# Sheet1.net
KiCad netlist of a schematic drawn in Altium Designer
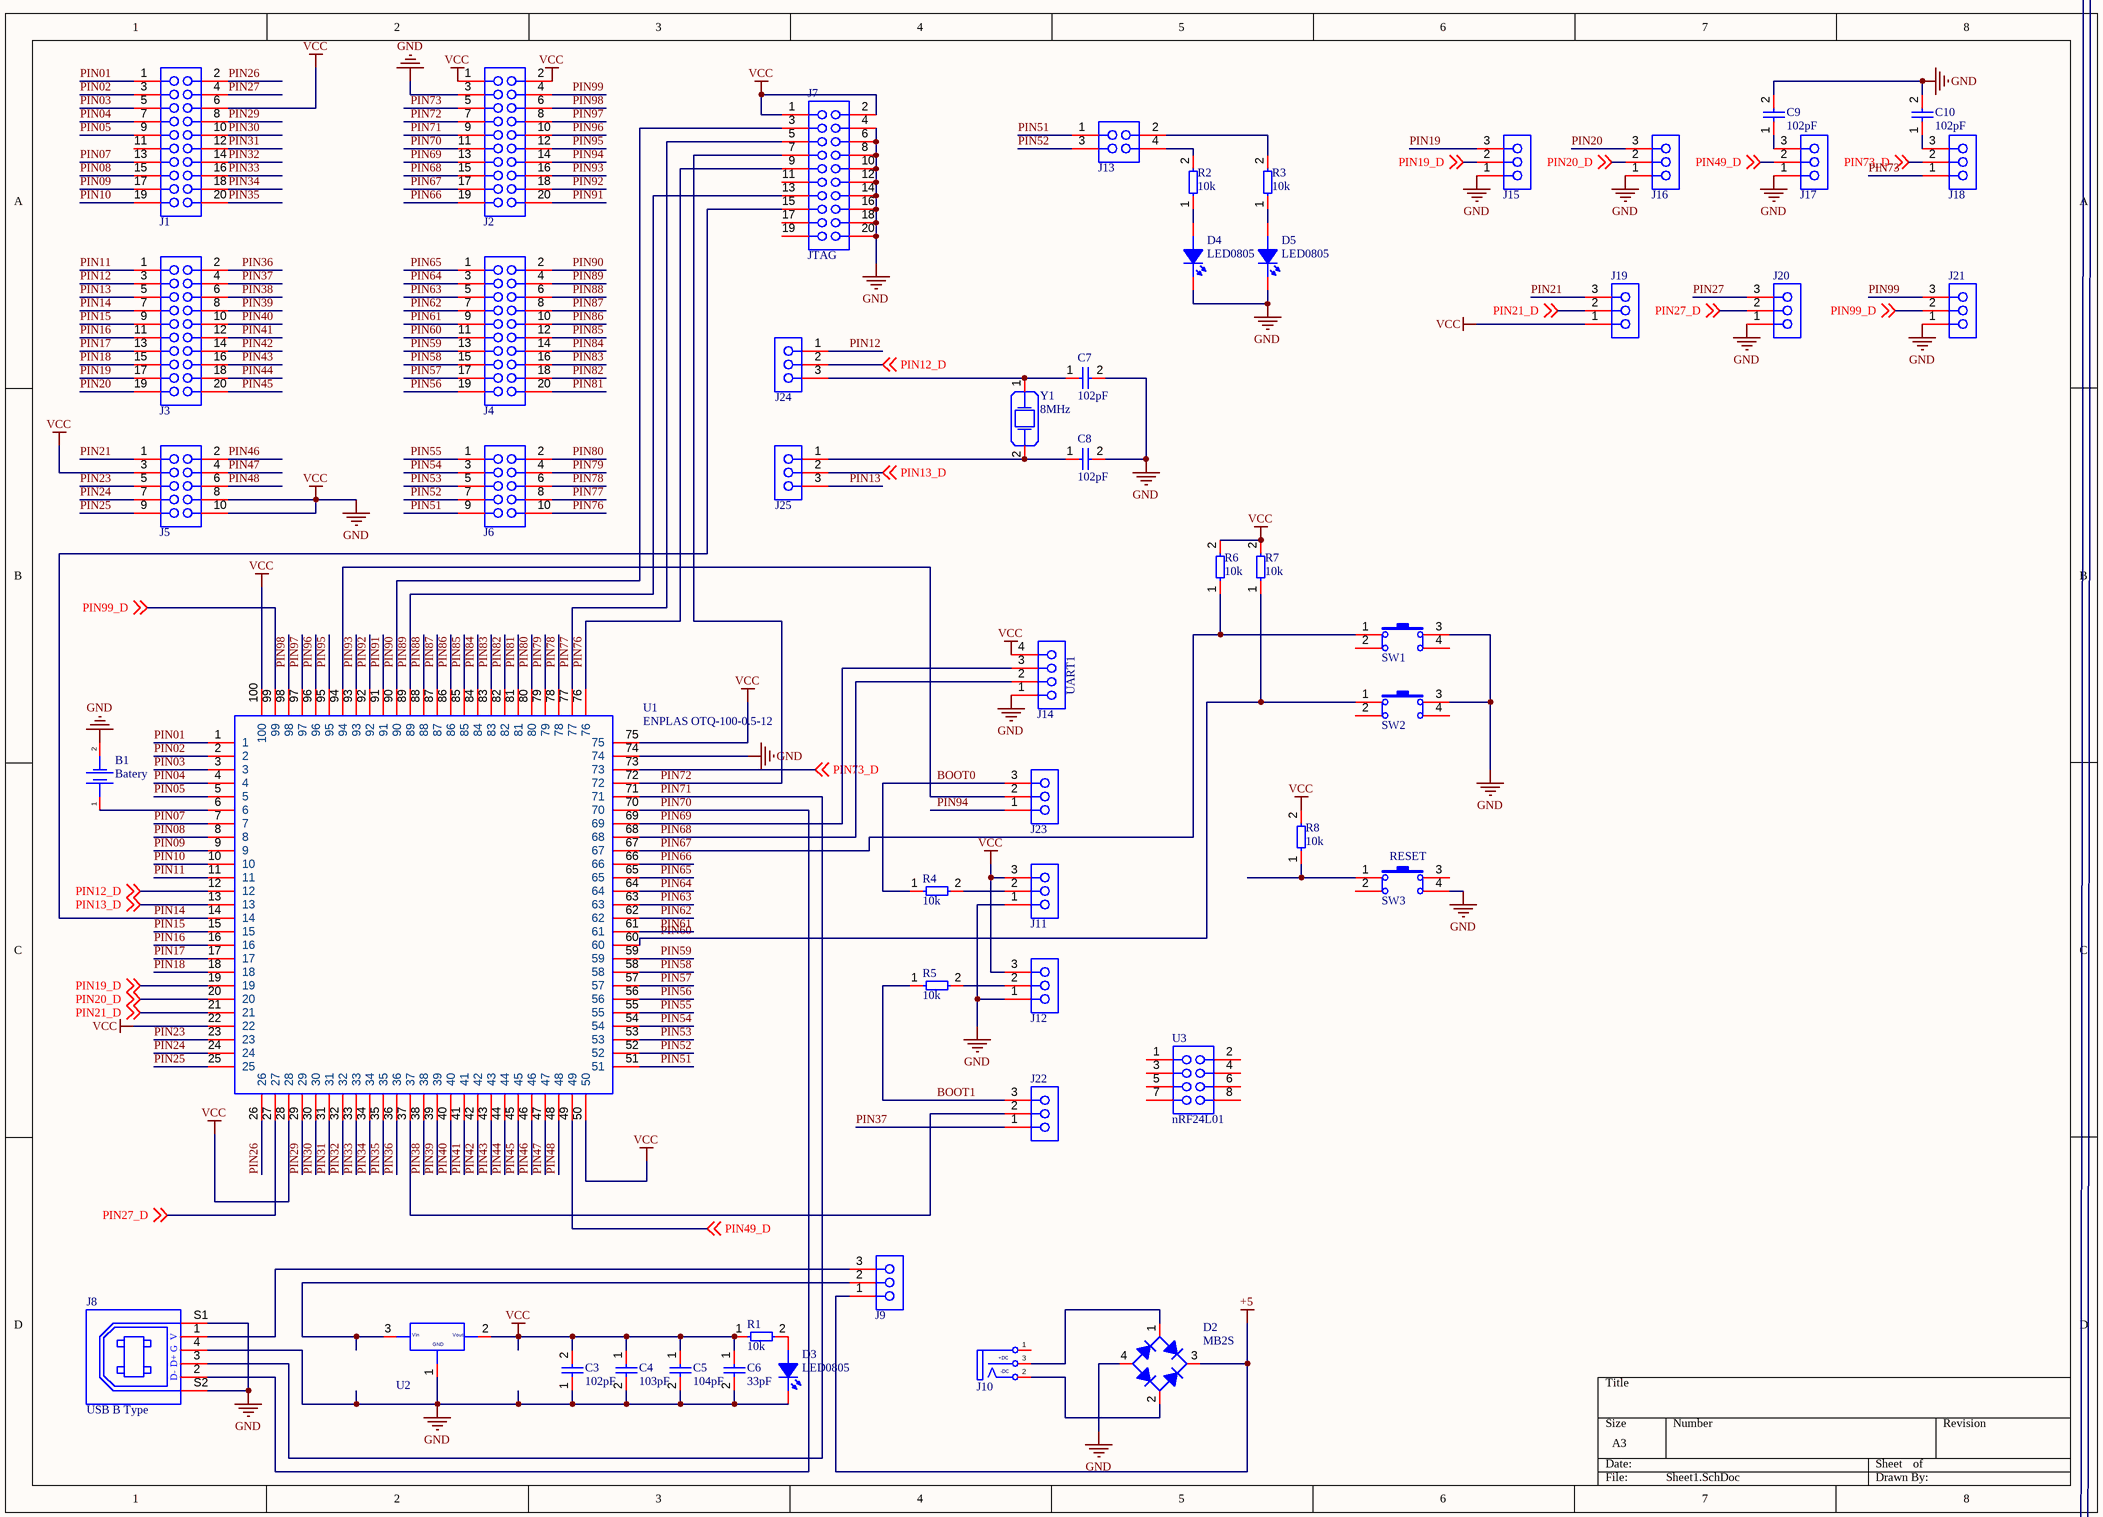
[diagram p0: Sheet1.SchDoc]

(export (version "E")
  (design (tool "Eeschema 10.0.6"))
  (components
    (comp (ref "B1") (value "Batery") (footprint "CR1220") (libsource (lib "SMDLibrary") (part "Batery")))
    (comp (ref "C3")
      (value "102pF")
      (footprint "C0805")
      (libsource (lib "SMDLibrary") (part "Capacitors(SMD)"))
    )
    (comp (ref "C4")
      (value "103pF")
      (footprint "C0805")
      (libsource (lib "SMDLibrary") (part "Capacitors(SMD)"))
    )
    (comp (ref "C5")
      (value "104pF")
      (footprint "C0805")
      (libsource (lib "SMDLibrary") (part "Capacitors(SMD)"))
    )
    (comp (ref "C6")
      (value "33pF")
      (footprint "C0805")
      (libsource (lib "SMDLibrary") (part "Capacitors(SMD)"))
    )
    (comp (ref "C7")
      (value "102pF")
      (footprint "C0805")
      (libsource (lib "SMDLibrary") (part "Capacitors(SMD)"))
    )
    (comp (ref "C8")
      (value "102pF")
      (footprint "C0805")
      (libsource (lib "SMDLibrary") (part "Capacitors(SMD)"))
    )
    (comp (ref "C9")
      (value "102pF")
      (footprint "C0805")
      (libsource (lib "SMDLibrary") (part "Capacitors(SMD)"))
    )
    (comp (ref "C10")
      (value "102pF")
      (footprint "C0805")
      (libsource (lib "SMDLibrary") (part "Capacitors(SMD)"))
    )
    (comp (ref "D2") (value "MB2S") (footprint "TO-269AA") (libsource (lib "SMDLibrary") (part "Diode MB2S")))
    (comp (ref "D3") (value "LED0805") (footprint "L0805RED") (libsource (lib "SMDLibrary") (part "LED0805")))
    (comp (ref "D4") (value "LED0805") (footprint "L0805RED") (libsource (lib "SMDLibrary") (part "LED0805")))
    (comp (ref "D5") (value "LED0805") (footprint "L0805RED") (libsource (lib "SMDLibrary") (part "LED0805")))
    (comp (ref "J1")
      (value "Header 10x2 TH Pitch 2.54mm")
      (footprint "Header 10x2 TH Pitch 2.54mm")
      (libsource (lib "SMDLibrary") (part "Header 10x2 TH Pitch 2.54mm"))
    )
    (comp (ref "J2")
      (value "Header 10x2 TH Pitch 2.54mm")
      (footprint "Header 10x2 TH Pitch 2.54mm")
      (libsource (lib "SMDLibrary") (part "Header 10x2 TH Pitch 2.54mm"))
    )
    (comp (ref "J3")
      (value "Header 10x2 TH Pitch 2.54mm")
      (footprint "Header 10x2 TH Pitch 2.54mm")
      (libsource (lib "SMDLibrary") (part "Header 10x2 TH Pitch 2.54mm"))
    )
    (comp (ref "J4")
      (value "Header 10x2 TH Pitch 2.54mm")
      (footprint "Header 10x2 TH Pitch 2.54mm")
      (libsource (lib "SMDLibrary") (part "Header 10x2 TH Pitch 2.54mm"))
    )
    (comp (ref "J5")
      (value "Header 5x2 TH Pitch 2.54mm")
      (footprint "Header 5x2 TH Pitch 2.54mm")
      (libsource (lib "SMDLibrary") (part "Header 5x2 TH Pitch 2.54mm"))
    )
    (comp (ref "J6")
      (value "Header 5x2 TH Pitch 2.54mm")
      (footprint "Header 5x2 TH Pitch 2.54mm")
      (libsource (lib "SMDLibrary") (part "Header 5x2 TH Pitch 2.54mm"))
    )
    (comp (ref "J7")
      (value "JTAG")
      (footprint "IDC_CONNECTOR_20_2.54")
      (libsource (lib "SMDLibrary") (part "IDC_2.54_10x2"))
    )
    (comp (ref "J8")
      (value "USB B Type")
      (footprint "USB-B-TYPE")
      (libsource (lib "SMDLibrary") (part "USB B Type"))
    )
    (comp (ref "J9")
      (value "Header 3x1 TH Pitch 2.54mm")
      (footprint "Header 3x1 TH Pitch 2.54mm")
      (libsource (lib "") (part "Header 3x1 TH Pitch 2.54mm_1"))
    )
    (comp (ref "J10")
      (value "Connector")
      (footprint "JACK-DC")
      (libsource (lib "SMDLibrary") (part "JackDC"))
    )
    (comp (ref "J11")
      (value "Header 3x1 TH Pitch 2.54mm")
      (footprint "Header 3x1 TH Pitch 2.54mm")
      (libsource (lib "") (part "Header 3x1 TH Pitch 2.54mm_1"))
    )
    (comp (ref "J12")
      (value "Header 3x1 TH Pitch 2.54mm")
      (footprint "Header 3x1 TH Pitch 2.54mm")
      (libsource (lib "") (part "Header 3x1 TH Pitch 2.54mm_1"))
    )
    (comp (ref "J13")
      (value "Header 2x2 TH Pitch 2.54mm")
      (footprint "Header 2x2 TH Pitch 2.54mm")
      (libsource (lib "SMDLibrary") (part "Header 2x2 TH Pitch 2.54mm"))
    )
    (comp (ref "J14")
      (value "UART1")
      (footprint "Header 4x1 TH Pitch 2.54mm")
      (libsource (lib "SMDLibrary") (part "Header 4x1 TH Pitch 2.54mm"))
    )
    (comp (ref "J15")
      (value "Header 3x1 TH Pitch 2.54mm")
      (footprint "Header 3x1 TH Pitch 2.54mm")
      (libsource (lib "") (part "Header 3x1 TH Pitch 2.54mm_1"))
    )
    (comp (ref "J16")
      (value "Header 3x1 TH Pitch 2.54mm")
      (footprint "Header 3x1 TH Pitch 2.54mm")
      (libsource (lib "") (part "Header 3x1 TH Pitch 2.54mm_1"))
    )
    (comp (ref "J17")
      (value "Header 3x1 TH Pitch 2.54mm")
      (footprint "Header 3x1 TH Pitch 2.54mm")
      (libsource (lib "") (part "Header 3x1 TH Pitch 2.54mm_1"))
    )
    (comp (ref "J18")
      (value "Header 3x1 TH Pitch 2.54mm")
      (footprint "Header 3x1 TH Pitch 2.54mm")
      (libsource (lib "") (part "Header 3x1 TH Pitch 2.54mm_1"))
    )
    (comp (ref "J19")
      (value "Header 3x1 TH Pitch 2.54mm")
      (footprint "Header 3x1 TH Pitch 2.54mm")
      (libsource (lib "") (part "Header 3x1 TH Pitch 2.54mm_1"))
    )
    (comp (ref "J20")
      (value "Header 3x1 TH Pitch 2.54mm")
      (footprint "Header 3x1 TH Pitch 2.54mm")
      (libsource (lib "") (part "Header 3x1 TH Pitch 2.54mm_1"))
    )
    (comp (ref "J21")
      (value "Header 3x1 TH Pitch 2.54mm")
      (footprint "Header 3x1 TH Pitch 2.54mm")
      (libsource (lib "") (part "Header 3x1 TH Pitch 2.54mm_1"))
    )
    (comp (ref "J22")
      (value "Header 3x1 TH Pitch 2.54mm")
      (footprint "Header 3x1 TH Pitch 2.54mm")
      (libsource (lib "") (part "Header 3x1 TH Pitch 2.54mm_1"))
    )
    (comp (ref "J23")
      (value "Header 3x1 TH Pitch 2.54mm")
      (footprint "Header 3x1 TH Pitch 2.54mm")
      (libsource (lib "") (part "Header 3x1 TH Pitch 2.54mm_1"))
    )
    (comp (ref "J24")
      (value "Header 3x1 TH Pitch 2.54mm")
      (footprint "Header 3x1 TH Pitch 2.54mm")
      (libsource (lib "SMDLibrary") (part "Header 3x1 TH Pitch 2.54mm"))
    )
    (comp (ref "J25")
      (value "Header 3x1 TH Pitch 2.54mm")
      (footprint "Header 3x1 TH Pitch 2.54mm")
      (libsource (lib "SMDLibrary") (part "Header 3x1 TH Pitch 2.54mm"))
    )
    (comp (ref "R1") (value "10k") (footprint "R0805") (libsource (lib "SMDLibrary") (part "Resistor SMD")))
    (comp (ref "R2") (value "10k") (footprint "R0805") (libsource (lib "") (part "Resistor SMD_1")))
    (comp (ref "R3") (value "10k") (footprint "R0805") (libsource (lib "") (part "Resistor SMD_1")))
    (comp (ref "R4") (value "10k") (footprint "R0805") (libsource (lib "SMDLibrary") (part "Resistor SMD")))
    (comp (ref "R5") (value "10k") (footprint "R0805") (libsource (lib "SMDLibrary") (part "Resistor SMD")))
    (comp (ref "R6") (value "10k") (footprint "R0805") (libsource (lib "") (part "Resistor SMD_1")))
    (comp (ref "R7") (value "10k") (footprint "R0805") (libsource (lib "") (part "Resistor SMD_1")))
    (comp (ref "R8") (value "10k") (footprint "R0805") (libsource (lib "") (part "Resistor SMD_1")))
    (comp (ref "SW1")
      (value "Button Hole")
      (footprint "BUTTON_HOLE_5.0mm")
      (libsource (lib "SMDLibrary") (part "Button Hole"))
    )
    (comp (ref "SW2")
      (value "Button Hole")
      (footprint "BUTTON_HOLE_5.0mm")
      (libsource (lib "SMDLibrary") (part "Button Hole"))
    )
    (comp (ref "SW3")
      (value "RESET")
      (footprint "BUTTON_HOLE_5.0mm")
      (libsource (lib "SMDLibrary") (part "Button Hole"))
    )
    (comp (ref "U1")
      (value "ENPLAS OTQ-100-0.5-12")
      (footprint "ENPLAS OTQ-100-0.5-12-00 IC SOCKET")
      (libsource (lib "SMDLibrary") (part "ENPLAS OTQ-100-0.5-12-00 IC SOCKET"))
    )
    (comp (ref "U2")
      (value "AMS1117")
      (footprint "SOT223-3")
      (libsource (lib "SMDLibrary") (part "AMS1117(SOT-223)"))
    )
    (comp (ref "U3")
      (value "nRF24L01")
      (footprint "nRF24L01")
      (libsource (lib "SMDLibrary") (part "nRF24L01"))
    )
    (comp (ref "Y1")
      (value "8MHz")
      (footprint "HC-49_THROUGH")
      (libsource (lib "SMDLibrary") (part "Crystal"))
    )
  )
  (nets
    (net (code "1") (name "+5") (class "Default")
      (node (ref "D2") (pin "3") (pinfunction "3_3") (pintype "passive"))
      (node (ref "J9") (pin "1") (pinfunction "1_1") (pintype "passive"))
    )
    (net (code "2") (name "/BOOT0") (class "Default")
      (node (ref "J23") (pin "3") (pinfunction "3_3") (pintype "passive"))
      (node (ref "R4") (pin "1") (pinfunction "1_1") (pintype "passive"))
    )
    (net (code "3") (name "/BOOT1") (class "Default")
      (node (ref "J22") (pin "3") (pinfunction "3_3") (pintype "passive"))
      (node (ref "R5") (pin "1") (pinfunction "1_1") (pintype "passive"))
    )
    (net (code "4") (name "/PIN01") (class "Default")
      (node (ref "J1") (pin "1") (pinfunction "1_1") (pintype "passive"))
      (node (ref "U1") (pin "1") (pinfunction "1_1") (pintype "passive"))
    )
    (net (code "5") (name "/PIN02") (class "Default")
      (node (ref "J1") (pin "3") (pinfunction "3_3") (pintype "passive"))
      (node (ref "U1") (pin "2") (pinfunction "2_2") (pintype "passive"))
    )
    (net (code "6") (name "/PIN03") (class "Default")
      (node (ref "J1") (pin "5") (pinfunction "5_5") (pintype "passive"))
      (node (ref "U1") (pin "3") (pinfunction "3_3") (pintype "passive"))
    )
    (net (code "7") (name "/PIN04") (class "Default")
      (node (ref "J1") (pin "7") (pinfunction "7_7") (pintype "passive"))
      (node (ref "U1") (pin "4") (pinfunction "4_4") (pintype "passive"))
    )
    (net (code "8") (name "/PIN05") (class "Default")
      (node (ref "J1") (pin "9") (pinfunction "9_9") (pintype "passive"))
      (node (ref "U1") (pin "5") (pinfunction "5_5") (pintype "passive"))
    )
    (net (code "9") (name "/PIN07") (class "Default")
      (node (ref "J1") (pin "13") (pinfunction "13_13") (pintype "passive"))
      (node (ref "U1") (pin "7") (pinfunction "7_7") (pintype "passive"))
    )
    (net (code "10") (name "/PIN08") (class "Default")
      (node (ref "J1") (pin "15") (pinfunction "15_15") (pintype "passive"))
      (node (ref "U1") (pin "8") (pinfunction "8_8") (pintype "passive"))
    )
    (net (code "11") (name "/PIN09") (class "Default")
      (node (ref "J1") (pin "17") (pinfunction "17_17") (pintype "passive"))
      (node (ref "U1") (pin "9") (pinfunction "9_9") (pintype "passive"))
    )
    (net (code "12") (name "/PIN10") (class "Default")
      (node (ref "J1") (pin "19") (pinfunction "19_19") (pintype "passive"))
      (node (ref "U1") (pin "10") (pinfunction "10_10") (pintype "passive"))
    )
    (net (code "13") (name "/PIN11") (class "Default")
      (node (ref "J3") (pin "1") (pinfunction "1_1") (pintype "passive"))
      (node (ref "U1") (pin "11") (pinfunction "11_11") (pintype "passive"))
    )
    (net (code "14") (name "/PIN12") (class "Default")
      (node (ref "J24") (pin "1") (pinfunction "1_1") (pintype "passive"))
      (node (ref "J3") (pin "3") (pinfunction "3_3") (pintype "passive"))
    )
    (net (code "15") (name "/PIN13") (class "Default")
      (node (ref "J25") (pin "3") (pinfunction "3_3") (pintype "passive"))
      (node (ref "J3") (pin "5") (pinfunction "5_5") (pintype "passive"))
    )
    (net (code "16") (name "/PIN14") (class "Default")
      (node (ref "J3") (pin "7") (pinfunction "7_7") (pintype "passive"))
      (node (ref "J7") (pin "15") (pinfunction "15_15") (pintype "passive"))
      (node (ref "U1") (pin "14") (pinfunction "14_14") (pintype "passive"))
    )
    (net (code "17") (name "/PIN15") (class "Default")
      (node (ref "J3") (pin "9") (pinfunction "9_9") (pintype "passive"))
      (node (ref "U1") (pin "15") (pinfunction "15_15") (pintype "passive"))
    )
    (net (code "18") (name "/PIN16") (class "Default")
      (node (ref "J3") (pin "11") (pinfunction "11_11") (pintype "passive"))
      (node (ref "U1") (pin "16") (pinfunction "16_16") (pintype "passive"))
    )
    (net (code "19") (name "/PIN17") (class "Default")
      (node (ref "J3") (pin "13") (pinfunction "13_13") (pintype "passive"))
      (node (ref "U1") (pin "17") (pinfunction "17_17") (pintype "passive"))
    )
    (net (code "20") (name "/PIN18") (class "Default")
      (node (ref "J3") (pin "15") (pinfunction "15_15") (pintype "passive"))
      (node (ref "U1") (pin "18") (pinfunction "18_18") (pintype "passive"))
    )
    (net (code "21") (name "/PIN19") (class "Default")
      (node (ref "J15") (pin "3") (pinfunction "3_3") (pintype "passive"))
      (node (ref "J3") (pin "17") (pinfunction "17_17") (pintype "passive"))
    )
    (net (code "22") (name "/PIN20") (class "Default")
      (node (ref "J16") (pin "3") (pinfunction "3_3") (pintype "passive"))
      (node (ref "J3") (pin "19") (pinfunction "19_19") (pintype "passive"))
    )
    (net (code "23") (name "/PIN21") (class "Default")
      (node (ref "J19") (pin "3") (pinfunction "3_3") (pintype "passive"))
      (node (ref "J5") (pin "1") (pinfunction "1_1") (pintype "passive"))
    )
    (net (code "24") (name "/PIN23") (class "Default")
      (node (ref "J5") (pin "5") (pinfunction "5_5") (pintype "passive"))
      (node (ref "U1") (pin "23") (pinfunction "23_23") (pintype "passive"))
    )
    (net (code "25") (name "/PIN24") (class "Default")
      (node (ref "J5") (pin "7") (pinfunction "7_7") (pintype "passive"))
      (node (ref "U1") (pin "24") (pinfunction "24_24") (pintype "passive"))
    )
    (net (code "26") (name "/PIN25") (class "Default")
      (node (ref "J5") (pin "9") (pinfunction "9_9") (pintype "passive"))
      (node (ref "U1") (pin "25") (pinfunction "25_25") (pintype "passive"))
    )
    (net (code "27") (name "/PIN26") (class "Default")
      (node (ref "J1") (pin "2") (pinfunction "2_2") (pintype "passive"))
      (node (ref "U1") (pin "26") (pinfunction "26_26") (pintype "passive"))
    )
    (net (code "28") (name "/PIN27") (class "Default")
      (node (ref "J1") (pin "4") (pinfunction "4_4") (pintype "passive"))
      (node (ref "J20") (pin "3") (pinfunction "3_3") (pintype "passive"))
    )
    (net (code "29") (name "/PIN29") (class "Default")
      (node (ref "J1") (pin "8") (pinfunction "8_8") (pintype "passive"))
      (node (ref "U1") (pin "29") (pinfunction "29_29") (pintype "passive"))
    )
    (net (code "30") (name "/PIN30") (class "Default")
      (node (ref "J1") (pin "10") (pinfunction "10_10") (pintype "passive"))
      (node (ref "U1") (pin "30") (pinfunction "30_30") (pintype "passive"))
    )
    (net (code "31") (name "/PIN31") (class "Default")
      (node (ref "J1") (pin "12") (pinfunction "12_12") (pintype "passive"))
      (node (ref "U1") (pin "31") (pinfunction "31_31") (pintype "passive"))
    )
    (net (code "32") (name "/PIN32") (class "Default")
      (node (ref "J1") (pin "14") (pinfunction "14_14") (pintype "passive"))
      (node (ref "U1") (pin "32") (pinfunction "32_32") (pintype "passive"))
    )
    (net (code "33") (name "/PIN33") (class "Default")
      (node (ref "J1") (pin "16") (pinfunction "16_16") (pintype "passive"))
      (node (ref "U1") (pin "33") (pinfunction "33_33") (pintype "passive"))
    )
    (net (code "34") (name "/PIN34") (class "Default")
      (node (ref "J1") (pin "18") (pinfunction "18_18") (pintype "passive"))
      (node (ref "U1") (pin "34") (pinfunction "34_34") (pintype "passive"))
    )
    (net (code "35") (name "/PIN35") (class "Default")
      (node (ref "J1") (pin "20") (pinfunction "20_20") (pintype "passive"))
      (node (ref "U1") (pin "35") (pinfunction "35_35") (pintype "passive"))
    )
    (net (code "36") (name "/PIN36") (class "Default")
      (node (ref "J3") (pin "2") (pinfunction "2_2") (pintype "passive"))
      (node (ref "U1") (pin "36") (pinfunction "36_36") (pintype "passive"))
    )
    (net (code "37") (name "/PIN37") (class "Default")
      (node (ref "J22") (pin "1") (pinfunction "1_1") (pintype "passive"))
      (node (ref "J3") (pin "4") (pinfunction "4_4") (pintype "passive"))
    )
    (net (code "38") (name "/PIN38") (class "Default")
      (node (ref "J3") (pin "6") (pinfunction "6_6") (pintype "passive"))
      (node (ref "U1") (pin "38") (pinfunction "38_38") (pintype "passive"))
    )
    (net (code "39") (name "/PIN39") (class "Default")
      (node (ref "J3") (pin "8") (pinfunction "8_8") (pintype "passive"))
      (node (ref "U1") (pin "39") (pinfunction "39_39") (pintype "passive"))
    )
    (net (code "40") (name "/PIN40") (class "Default")
      (node (ref "J3") (pin "10") (pinfunction "10_10") (pintype "passive"))
      (node (ref "U1") (pin "40") (pinfunction "40_40") (pintype "passive"))
    )
    (net (code "41") (name "/PIN41") (class "Default")
      (node (ref "J3") (pin "12") (pinfunction "12_12") (pintype "passive"))
      (node (ref "U1") (pin "41") (pinfunction "41_41") (pintype "passive"))
    )
    (net (code "42") (name "/PIN42") (class "Default")
      (node (ref "J3") (pin "14") (pinfunction "14_14") (pintype "passive"))
      (node (ref "U1") (pin "42") (pinfunction "42_42") (pintype "passive"))
    )
    (net (code "43") (name "/PIN43") (class "Default")
      (node (ref "J3") (pin "16") (pinfunction "16_16") (pintype "passive"))
      (node (ref "U1") (pin "43") (pinfunction "43_43") (pintype "passive"))
    )
    (net (code "44") (name "/PIN44") (class "Default")
      (node (ref "J3") (pin "18") (pinfunction "18_18") (pintype "passive"))
      (node (ref "U1") (pin "44") (pinfunction "44_44") (pintype "passive"))
    )
    (net (code "45") (name "/PIN45") (class "Default")
      (node (ref "J3") (pin "20") (pinfunction "20_20") (pintype "passive"))
      (node (ref "U1") (pin "45") (pinfunction "45_45") (pintype "passive"))
    )
    (net (code "46") (name "/PIN46") (class "Default")
      (node (ref "J5") (pin "2") (pinfunction "2_2") (pintype "passive"))
      (node (ref "U1") (pin "46") (pinfunction "46_46") (pintype "passive"))
    )
    (net (code "47") (name "/PIN47") (class "Default")
      (node (ref "J5") (pin "4") (pinfunction "4_4") (pintype "passive"))
      (node (ref "U1") (pin "47") (pinfunction "47_47") (pintype "passive"))
    )
    (net (code "48") (name "/PIN48") (class "Default")
      (node (ref "J5") (pin "6") (pinfunction "6_6") (pintype "passive"))
      (node (ref "U1") (pin "48") (pinfunction "48_48") (pintype "passive"))
    )
    (net (code "49") (name "/PIN51") (class "Default")
      (node (ref "J13") (pin "1") (pinfunction "1_1") (pintype "passive"))
      (node (ref "J6") (pin "9") (pinfunction "9_9") (pintype "passive"))
      (node (ref "U1") (pin "51") (pinfunction "51_51") (pintype "passive"))
    )
    (net (code "50") (name "/PIN52") (class "Default")
      (node (ref "J13") (pin "3") (pinfunction "3_3") (pintype "passive"))
      (node (ref "J6") (pin "7") (pinfunction "7_7") (pintype "passive"))
      (node (ref "U1") (pin "52") (pinfunction "52_52") (pintype "passive"))
    )
    (net (code "51") (name "/PIN53") (class "Default")
      (node (ref "J6") (pin "5") (pinfunction "5_5") (pintype "passive"))
      (node (ref "U1") (pin "53") (pinfunction "53_53") (pintype "passive"))
    )
    (net (code "52") (name "/PIN54") (class "Default")
      (node (ref "J6") (pin "3") (pinfunction "3_3") (pintype "passive"))
      (node (ref "U1") (pin "54") (pinfunction "54_54") (pintype "passive"))
    )
    (net (code "53") (name "/PIN55") (class "Default")
      (node (ref "J6") (pin "1") (pinfunction "1_1") (pintype "passive"))
      (node (ref "U1") (pin "55") (pinfunction "55_55") (pintype "passive"))
    )
    (net (code "54") (name "/PIN56") (class "Default")
      (node (ref "J4") (pin "19") (pinfunction "19_19") (pintype "passive"))
      (node (ref "U1") (pin "56") (pinfunction "56_56") (pintype "passive"))
    )
    (net (code "55") (name "/PIN57") (class "Default")
      (node (ref "J4") (pin "17") (pinfunction "17_17") (pintype "passive"))
      (node (ref "U1") (pin "57") (pinfunction "57_57") (pintype "passive"))
    )
    (net (code "56") (name "/PIN58") (class "Default")
      (node (ref "J4") (pin "15") (pinfunction "15_15") (pintype "passive"))
      (node (ref "U1") (pin "58") (pinfunction "58_58") (pintype "passive"))
    )
    (net (code "57") (name "/PIN59") (class "Default")
      (node (ref "J4") (pin "13") (pinfunction "13_13") (pintype "passive"))
      (node (ref "U1") (pin "59") (pinfunction "59_59") (pintype "passive"))
    )
    (net (code "58") (name "/PIN60") (class "Default")
      (node (ref "J4") (pin "11") (pinfunction "11_11") (pintype "passive"))
      (node (ref "R7") (pin "1") (pinfunction "1_1") (pintype "passive"))
      (node (ref "SW2") (pin "1") (pinfunction "1_1") (pintype "passive"))
      (node (ref "U1") (pin "60") (pinfunction "60_60") (pintype "passive"))
    )
    (net (code "59") (name "/PIN61") (class "Default")
      (node (ref "J4") (pin "9") (pinfunction "9_9") (pintype "passive"))
      (node (ref "U1") (pin "61") (pinfunction "61_61") (pintype "passive"))
    )
    (net (code "60") (name "/PIN62") (class "Default")
      (node (ref "J4") (pin "7") (pinfunction "7_7") (pintype "passive"))
      (node (ref "U1") (pin "62") (pinfunction "62_62") (pintype "passive"))
    )
    (net (code "61") (name "/PIN63") (class "Default")
      (node (ref "J4") (pin "5") (pinfunction "5_5") (pintype "passive"))
      (node (ref "U1") (pin "63") (pinfunction "63_63") (pintype "passive"))
    )
    (net (code "62") (name "/PIN64") (class "Default")
      (node (ref "J4") (pin "3") (pinfunction "3_3") (pintype "passive"))
      (node (ref "U1") (pin "64") (pinfunction "64_64") (pintype "passive"))
    )
    (net (code "63") (name "/PIN65") (class "Default")
      (node (ref "J4") (pin "1") (pinfunction "1_1") (pintype "passive"))
      (node (ref "U1") (pin "65") (pinfunction "65_65") (pintype "passive"))
    )
    (net (code "64") (name "/PIN66") (class "Default")
      (node (ref "J2") (pin "19") (pinfunction "19_19") (pintype "passive"))
      (node (ref "U1") (pin "66") (pinfunction "66_66") (pintype "passive"))
    )
    (net (code "65") (name "/PIN67") (class "Default")
      (node (ref "J2") (pin "17") (pinfunction "17_17") (pintype "passive"))
      (node (ref "R6") (pin "1") (pinfunction "1_1") (pintype "passive"))
      (node (ref "SW1") (pin "1") (pinfunction "1_1") (pintype "passive"))
      (node (ref "U1") (pin "67") (pinfunction "67_67") (pintype "passive"))
    )
    (net (code "66") (name "/PIN68") (class "Default")
      (node (ref "J14") (pin "2") (pinfunction "2_2") (pintype "passive"))
      (node (ref "J2") (pin "15") (pinfunction "15_15") (pintype "passive"))
      (node (ref "U1") (pin "68") (pinfunction "68_68") (pintype "passive"))
    )
    (net (code "67") (name "/PIN69") (class "Default")
      (node (ref "J14") (pin "3") (pinfunction "3_3") (pintype "passive"))
      (node (ref "J2") (pin "13") (pinfunction "13_13") (pintype "passive"))
      (node (ref "U1") (pin "69") (pinfunction "69_69") (pintype "passive"))
    )
    (net (code "68") (name "/PIN70") (class "Default")
      (node (ref "J2") (pin "11") (pinfunction "11_11") (pintype "passive"))
      (node (ref "J8") (pin "2") (pinfunction "2_2") (pintype "passive"))
      (node (ref "U1") (pin "70") (pinfunction "70_70") (pintype "passive"))
    )
    (net (code "69") (name "/PIN71") (class "Default")
      (node (ref "J2") (pin "9") (pinfunction "9_9") (pintype "passive"))
      (node (ref "J8") (pin "3") (pinfunction "3_3") (pintype "passive"))
      (node (ref "U1") (pin "71") (pinfunction "71_71") (pintype "passive"))
    )
    (net (code "70") (name "/PIN72") (class "Default")
      (node (ref "J2") (pin "7") (pinfunction "7_7") (pintype "passive"))
      (node (ref "J7") (pin "7") (pinfunction "7_7") (pintype "passive"))
      (node (ref "U1") (pin "72") (pinfunction "72_72") (pintype "passive"))
    )
    (net (code "71") (name "/PIN73") (class "Default")
      (node (ref "J18") (pin "1") (pinfunction "1_1") (pintype "passive"))
      (node (ref "J2") (pin "5") (pinfunction "5_5") (pintype "passive"))
    )
    (net (code "72") (name "/PIN76") (class "Default")
      (node (ref "J6") (pin "10") (pinfunction "10_10") (pintype "passive"))
      (node (ref "J7") (pin "9") (pinfunction "9_9") (pintype "passive"))
      (node (ref "U1") (pin "76") (pinfunction "76_76") (pintype "passive"))
    )
    (net (code "73") (name "/PIN77") (class "Default")
      (node (ref "J6") (pin "8") (pinfunction "8_8") (pintype "passive"))
      (node (ref "J7") (pin "5") (pinfunction "5_5") (pintype "passive"))
      (node (ref "U1") (pin "77") (pinfunction "77_77") (pintype "passive"))
    )
    (net (code "74") (name "/PIN78") (class "Default")
      (node (ref "J6") (pin "6") (pinfunction "6_6") (pintype "passive"))
      (node (ref "U1") (pin "78") (pinfunction "78_78") (pintype "passive"))
    )
    (net (code "75") (name "/PIN79") (class "Default")
      (node (ref "J6") (pin "4") (pinfunction "4_4") (pintype "passive"))
      (node (ref "U1") (pin "79") (pinfunction "79_79") (pintype "passive"))
    )
    (net (code "76") (name "/PIN80") (class "Default")
      (node (ref "J6") (pin "2") (pinfunction "2_2") (pintype "passive"))
      (node (ref "U1") (pin "80") (pinfunction "80_80") (pintype "passive"))
    )
    (net (code "77") (name "/PIN81") (class "Default")
      (node (ref "J4") (pin "20") (pinfunction "20_20") (pintype "passive"))
      (node (ref "U1") (pin "81") (pinfunction "81_81") (pintype "passive"))
    )
    (net (code "78") (name "/PIN82") (class "Default")
      (node (ref "J4") (pin "18") (pinfunction "18_18") (pintype "passive"))
      (node (ref "U1") (pin "82") (pinfunction "82_82") (pintype "passive"))
    )
    (net (code "79") (name "/PIN83") (class "Default")
      (node (ref "J4") (pin "16") (pinfunction "16_16") (pintype "passive"))
      (node (ref "U1") (pin "83") (pinfunction "83_83") (pintype "passive"))
    )
    (net (code "80") (name "/PIN84") (class "Default")
      (node (ref "J4") (pin "14") (pinfunction "14_14") (pintype "passive"))
      (node (ref "U1") (pin "84") (pinfunction "84_84") (pintype "passive"))
    )
    (net (code "81") (name "/PIN85") (class "Default")
      (node (ref "J4") (pin "12") (pinfunction "12_12") (pintype "passive"))
      (node (ref "U1") (pin "85") (pinfunction "85_85") (pintype "passive"))
    )
    (net (code "82") (name "/PIN86") (class "Default")
      (node (ref "J4") (pin "10") (pinfunction "10_10") (pintype "passive"))
      (node (ref "U1") (pin "86") (pinfunction "86_86") (pintype "passive"))
    )
    (net (code "83") (name "/PIN87") (class "Default")
      (node (ref "J4") (pin "8") (pinfunction "8_8") (pintype "passive"))
      (node (ref "U1") (pin "87") (pinfunction "87_87") (pintype "passive"))
    )
    (net (code "84") (name "/PIN88") (class "Default")
      (node (ref "J4") (pin "6") (pinfunction "6_6") (pintype "passive"))
      (node (ref "U1") (pin "88") (pinfunction "88_88") (pintype "passive"))
    )
    (net (code "85") (name "/PIN89") (class "Default")
      (node (ref "J4") (pin "4") (pinfunction "4_4") (pintype "passive"))
      (node (ref "J7") (pin "13") (pinfunction "13_13") (pintype "passive"))
      (node (ref "U1") (pin "89") (pinfunction "89_89") (pintype "passive"))
    )
    (net (code "86") (name "/PIN90") (class "Default")
      (node (ref "J4") (pin "2") (pinfunction "2_2") (pintype "passive"))
      (node (ref "J7") (pin "3") (pinfunction "3_3") (pintype "passive"))
      (node (ref "U1") (pin "90") (pinfunction "90_90") (pintype "passive"))
    )
    (net (code "87") (name "/PIN91") (class "Default")
      (node (ref "J2") (pin "20") (pinfunction "20_20") (pintype "passive"))
      (node (ref "U1") (pin "91") (pinfunction "91_91") (pintype "passive"))
    )
    (net (code "88") (name "/PIN92") (class "Default")
      (node (ref "J2") (pin "18") (pinfunction "18_18") (pintype "passive"))
      (node (ref "U1") (pin "92") (pinfunction "92_92") (pintype "passive"))
    )
    (net (code "89") (name "/PIN93") (class "Default")
      (node (ref "J2") (pin "16") (pinfunction "16_16") (pintype "passive"))
      (node (ref "U1") (pin "93") (pinfunction "93_93") (pintype "passive"))
    )
    (net (code "90") (name "/PIN94") (class "Default")
      (node (ref "J2") (pin "14") (pinfunction "14_14") (pintype "passive"))
      (node (ref "J23") (pin "1") (pinfunction "1_1") (pintype "passive"))
    )
    (net (code "91") (name "/PIN95") (class "Default")
      (node (ref "J2") (pin "12") (pinfunction "12_12") (pintype "passive"))
      (node (ref "U1") (pin "95") (pinfunction "95_95") (pintype "passive"))
    )
    (net (code "92") (name "/PIN96") (class "Default")
      (node (ref "J2") (pin "10") (pinfunction "10_10") (pintype "passive"))
      (node (ref "U1") (pin "96") (pinfunction "96_96") (pintype "passive"))
    )
    (net (code "93") (name "/PIN97") (class "Default")
      (node (ref "J2") (pin "8") (pinfunction "8_8") (pintype "passive"))
      (node (ref "U1") (pin "97") (pinfunction "97_97") (pintype "passive"))
    )
    (net (code "94") (name "/PIN98") (class "Default")
      (node (ref "J2") (pin "6") (pinfunction "6_6") (pintype "passive"))
      (node (ref "U1") (pin "98") (pinfunction "98_98") (pintype "passive"))
    )
    (net (code "95") (name "/PIN99") (class "Default")
      (node (ref "J2") (pin "4") (pinfunction "4_4") (pintype "passive"))
      (node (ref "J21") (pin "3") (pinfunction "3_3") (pintype "passive"))
    )
    (net (code "96") (name "GND") (class "Default")
      (node (ref "B1") (pin "2") (pinfunction "2_2") (pintype "passive"))
      (node (ref "C10") (pin "2") (pinfunction "2_2") (pintype "passive"))
      (node (ref "C3") (pin "1") (pinfunction "1_1") (pintype "passive"))
      (node (ref "C3") (pin "2") (pinfunction "2_2") (pintype "passive"))
      (node (ref "C4") (pin "1") (pinfunction "1_1") (pintype "passive"))
      (node (ref "C4") (pin "2") (pinfunction "2_2") (pintype "passive"))
      (node (ref "C5") (pin "1") (pinfunction "1_1") (pintype "passive"))
      (node (ref "C5") (pin "2") (pinfunction "2_2") (pintype "passive"))
      (node (ref "C6") (pin "1") (pinfunction "1_1") (pintype "passive"))
      (node (ref "C6") (pin "2") (pinfunction "2_2") (pintype "passive"))
      (node (ref "C7") (pin "2") (pinfunction "2_2") (pintype "passive"))
      (node (ref "C8") (pin "2") (pinfunction "2_2") (pintype "passive"))
      (node (ref "C9") (pin "2") (pinfunction "2_2") (pintype "passive"))
      (node (ref "D2") (pin "4") (pinfunction "4_4") (pintype "passive"))
      (node (ref "D3") (pin "2") (pinfunction "K_2") (pintype "passive"))
      (node (ref "D4") (pin "2") (pinfunction "K_2") (pintype "passive"))
      (node (ref "D5") (pin "2") (pinfunction "K_2") (pintype "passive"))
      (node (ref "J1") (pin "6") (pinfunction "6_6") (pintype "passive"))
      (node (ref "J11") (pin "1") (pinfunction "1_1") (pintype "passive"))
      (node (ref "J11") (pin "3") (pinfunction "3_3") (pintype "passive"))
      (node (ref "J12") (pin "1") (pinfunction "1_1") (pintype "passive"))
      (node (ref "J12") (pin "3") (pinfunction "3_3") (pintype "passive"))
      (node (ref "J14") (pin "1") (pinfunction "1_1") (pintype "passive"))
      (node (ref "J14") (pin "4") (pinfunction "4_4") (pintype "passive"))
      (node (ref "J15") (pin "1") (pinfunction "1_1") (pintype "passive"))
      (node (ref "J16") (pin "1") (pinfunction "1_1") (pintype "passive"))
      (node (ref "J17") (pin "1") (pinfunction "1_1") (pintype "passive"))
      (node (ref "J19") (pin "1") (pinfunction "1_1") (pintype "passive"))
      (node (ref "J2") (pin "1") (pinfunction "1_1") (pintype "passive"))
      (node (ref "J2") (pin "2") (pinfunction "2_2") (pintype "passive"))
      (node (ref "J2") (pin "3") (pinfunction "3_3") (pintype "passive"))
      (node (ref "J20") (pin "1") (pinfunction "1_1") (pintype "passive"))
      (node (ref "J21") (pin "1") (pinfunction "1_1") (pintype "passive"))
      (node (ref "J5") (pin "10") (pinfunction "10_10") (pintype "passive"))
      (node (ref "J5") (pin "3") (pinfunction "3_3") (pintype "passive"))
      (node (ref "J5") (pin "8") (pinfunction "8_8") (pintype "passive"))
      (node (ref "J7") (pin "1") (pinfunction "1_1") (pintype "passive"))
      (node (ref "J7") (pin "10") (pinfunction "10_10") (pintype "passive"))
      (node (ref "J7") (pin "12") (pinfunction "12_12") (pintype "passive"))
      (node (ref "J7") (pin "14") (pinfunction "14_14") (pintype "passive"))
      (node (ref "J7") (pin "16") (pinfunction "16_16") (pintype "passive"))
      (node (ref "J7") (pin "18") (pinfunction "18_18") (pintype "passive"))
      (node (ref "J7") (pin "2") (pinfunction "2_2") (pintype "passive"))
      (node (ref "J7") (pin "20") (pinfunction "20_20") (pintype "passive"))
      (node (ref "J7") (pin "4") (pinfunction "4_4") (pintype "passive"))
      (node (ref "J7") (pin "6") (pinfunction "6_6") (pintype "passive"))
      (node (ref "J7") (pin "8") (pinfunction "8_8") (pintype "passive"))
      (node (ref "J8") (pin "4") (pinfunction "4_4") (pintype "passive"))
      (node (ref "J8") (pin "S1") (pinfunction "S1_S1") (pintype "passive"))
      (node (ref "J8") (pin "S2") (pinfunction "S2_S2") (pintype "passive"))
      (node (ref "R1") (pin "1") (pinfunction "1_1") (pintype "passive"))
      (node (ref "R6") (pin "2") (pinfunction "2_2") (pintype "passive"))
      (node (ref "R7") (pin "2") (pinfunction "2_2") (pintype "passive"))
      (node (ref "R8") (pin "2") (pinfunction "2_2") (pintype "passive"))
      (node (ref "SW1") (pin "3") (pinfunction "3_3") (pintype "passive"))
      (node (ref "SW2") (pin "3") (pinfunction "3_3") (pintype "passive"))
      (node (ref "SW3") (pin "4") (pinfunction "4_4") (pintype "passive"))
      (node (ref "U1") (pin "100") (pinfunction "100_100") (pintype "passive"))
      (node (ref "U1") (pin "22") (pinfunction "22_22") (pintype "passive"))
      (node (ref "U1") (pin "28") (pinfunction "28_28") (pintype "passive"))
      (node (ref "U1") (pin "50") (pinfunction "50_50") (pintype "passive"))
      (node (ref "U1") (pin "74") (pinfunction "74_74") (pintype "passive"))
      (node (ref "U1") (pin "75") (pinfunction "75_75") (pintype "passive"))
      (node (ref "U2") (pin "1") (pinfunction "1_1") (pintype "passive"))
      (node (ref "U2") (pin "2") (pinfunction "2_2") (pintype "passive"))
    )
    (net (code "97") (name "Net-(B1-Pad1)") (class "Default")
      (node (ref "B1") (pin "1") (pinfunction "1_1") (pintype "passive"))
      (node (ref "U1") (pin "6") (pinfunction "6_6") (pintype "passive"))
    )
    (net (code "98") (name "Net-(C7-Pad1)") (class "Default")
      (node (ref "C7") (pin "1") (pinfunction "1_1") (pintype "passive"))
      (node (ref "J24") (pin "3") (pinfunction "3_3") (pintype "passive"))
      (node (ref "Y1") (pin "1") (pinfunction "1_1") (pintype "passive"))
    )
    (net (code "99") (name "Net-(C8-Pad1)") (class "Default")
      (node (ref "C8") (pin "1") (pinfunction "1_1") (pintype "passive"))
      (node (ref "J25") (pin "1") (pinfunction "1_1") (pintype "passive"))
      (node (ref "Y1") (pin "2") (pinfunction "2_2") (pintype "passive"))
    )
    (net (code "100") (name "Net-(C9-Pad1)") (class "Default")
      (node (ref "C9") (pin "1") (pinfunction "1_1") (pintype "passive"))
      (node (ref "J17") (pin "3") (pinfunction "3_3") (pintype "passive"))
    )
    (net (code "101") (name "Net-(C10-Pad1)") (class "Default")
      (node (ref "C10") (pin "1") (pinfunction "1_1") (pintype "passive"))
      (node (ref "J18") (pin "3") (pinfunction "3_3") (pintype "passive"))
    )
    (net (code "102") (name "Net-(D3-A)") (class "Default")
      (node (ref "D3") (pin "1") (pinfunction "A_1") (pintype "passive"))
      (node (ref "R1") (pin "2") (pinfunction "2_2") (pintype "passive"))
    )
    (net (code "103") (name "Net-(D4-A)") (class "Default")
      (node (ref "D4") (pin "1") (pinfunction "A_1") (pintype "passive"))
      (node (ref "R2") (pin "1") (pinfunction "1_1") (pintype "passive"))
    )
    (net (code "104") (name "Net-(D5-A)") (class "Default")
      (node (ref "D5") (pin "1") (pinfunction "A_1") (pintype "passive"))
      (node (ref "R3") (pin "1") (pinfunction "1_1") (pintype "passive"))
    )
    (net (code "105") (name "Net-(J8-Pad1)") (class "Default")
      (node (ref "J8") (pin "1") (pinfunction "1_1") (pintype "passive"))
      (node (ref "J9") (pin "3") (pinfunction "3_3") (pintype "passive"))
    )
    (net (code "106") (name "Net-(J9-Pad2)") (class "Default")
      (node (ref "J9") (pin "2") (pinfunction "2_2") (pintype "passive"))
      (node (ref "U2") (pin "3") (pinfunction "3_3") (pintype "passive"))
    )
    (net (code "107") (name "Net-(J10-S)") (class "Default")
      (node (ref "D2") (pin "1") (pinfunction "1_1") (pintype "passive"))
      (node (ref "J10") (pin "3") (pinfunction "S_3") (pintype "power_in"))
    )
    (net (code "108") (name "Net-(J10-TN)") (class "Default")
      (node (ref "D2") (pin "2") (pinfunction "2_2") (pintype "passive"))
      (node (ref "J10") (pin "2") (pinfunction "TN_2") (pintype "passive"))
    )
    (net (code "109") (name "Net-(J11-Pad2)") (class "Default")
      (node (ref "J11") (pin "2") (pinfunction "2_2") (pintype "passive"))
      (node (ref "R4") (pin "2") (pinfunction "2_2") (pintype "passive"))
    )
    (net (code "110") (name "Net-(J12-Pad2)") (class "Default")
      (node (ref "J12") (pin "2") (pinfunction "2_2") (pintype "passive"))
      (node (ref "R5") (pin "2") (pinfunction "2_2") (pintype "passive"))
    )
    (net (code "111") (name "Net-(J13-Pad2)") (class "Default")
      (node (ref "J13") (pin "2") (pinfunction "2_2") (pintype "passive"))
      (node (ref "R3") (pin "2") (pinfunction "2_2") (pintype "passive"))
    )
    (net (code "112") (name "Net-(J13-Pad4)") (class "Default")
      (node (ref "J13") (pin "4") (pinfunction "4_4") (pintype "passive"))
      (node (ref "R2") (pin "2") (pinfunction "2_2") (pintype "passive"))
    )
    (net (code "113") (name "Net-(J22-Pad2)") (class "Default")
      (node (ref "J22") (pin "2") (pinfunction "2_2") (pintype "passive"))
      (node (ref "U1") (pin "37") (pinfunction "37_37") (pintype "passive"))
    )
    (net (code "114") (name "Net-(J23-Pad2)") (class "Default")
      (node (ref "J23") (pin "2") (pinfunction "2_2") (pintype "passive"))
      (node (ref "U1") (pin "94") (pinfunction "94_94") (pintype "passive"))
    )
    (net (code "115") (name "Net-(R8-Pad1)") (class "Default")
      (node (ref "R8") (pin "1") (pinfunction "1_1") (pintype "passive"))
      (node (ref "SW3") (pin "1") (pinfunction "1_1") (pintype "passive"))
    )
    (net (code "116") (name "PIN12_D") (class "Default")
      (node (ref "J24") (pin "2") (pinfunction "2_2") (pintype "passive"))
      (node (ref "U1") (pin "12") (pinfunction "12_12") (pintype "passive"))
    )
    (net (code "117") (name "PIN13_D") (class "Default")
      (node (ref "J25") (pin "2") (pinfunction "2_2") (pintype "passive"))
      (node (ref "U1") (pin "13") (pinfunction "13_13") (pintype "passive"))
    )
    (net (code "118") (name "PIN19_D") (class "Default")
      (node (ref "J15") (pin "2") (pinfunction "2_2") (pintype "passive"))
      (node (ref "U1") (pin "19") (pinfunction "19_19") (pintype "passive"))
    )
    (net (code "119") (name "PIN20_D") (class "Default")
      (node (ref "J16") (pin "2") (pinfunction "2_2") (pintype "passive"))
      (node (ref "U1") (pin "20") (pinfunction "20_20") (pintype "passive"))
    )
    (net (code "120") (name "PIN21_D") (class "Default")
      (node (ref "J19") (pin "2") (pinfunction "2_2") (pintype "passive"))
      (node (ref "U1") (pin "21") (pinfunction "21_21") (pintype "passive"))
    )
    (net (code "121") (name "PIN27_D") (class "Default")
      (node (ref "J20") (pin "2") (pinfunction "2_2") (pintype "passive"))
      (node (ref "U1") (pin "27") (pinfunction "27_27") (pintype "passive"))
    )
    (net (code "122") (name "PIN49_D") (class "Default")
      (node (ref "J17") (pin "2") (pinfunction "2_2") (pintype "passive"))
      (node (ref "U1") (pin "49") (pinfunction "49_49") (pintype "passive"))
    )
    (net (code "123") (name "PIN73_D") (class "Default")
      (node (ref "J18") (pin "2") (pinfunction "2_2") (pintype "passive"))
      (node (ref "U1") (pin "73") (pinfunction "73_73") (pintype "passive"))
    )
    (net (code "124") (name "PIN99_D") (class "Default")
      (node (ref "J21") (pin "2") (pinfunction "2_2") (pintype "passive"))
      (node (ref "U1") (pin "99") (pinfunction "99_99") (pintype "passive"))
    )
    (net (code "125") (name "unconnected-(J1-Pad11)") (class "Default")
      (node (ref "J1") (pin "11") (pinfunction "11_11") (pintype "passive"))
    )
    (net (code "126") (name "unconnected-(J7-Pad11)") (class "Default")
      (node (ref "J7") (pin "11") (pinfunction "11_11") (pintype "passive"))
    )
    (net (code "127") (name "unconnected-(J7-Pad17)") (class "Default")
      (node (ref "J7") (pin "17") (pinfunction "17_17") (pintype "passive"))
    )
    (net (code "128") (name "unconnected-(J7-Pad19)") (class "Default")
      (node (ref "J7") (pin "19") (pinfunction "19_19") (pintype "passive"))
    )
    (net (code "129") (name "unconnected-(J10-T-Pad1)") (class "Default")
      (node (ref "J10") (pin "1") (pinfunction "T_1") (pintype "passive"))
    )
    (net (code "130") (name "unconnected-(SW1-Pad2)") (class "Default")
      (node (ref "SW1") (pin "2") (pinfunction "2_2") (pintype "passive"))
    )
    (net (code "131") (name "unconnected-(SW1-Pad4)") (class "Default")
      (node (ref "SW1") (pin "4") (pinfunction "4_4") (pintype "passive"))
    )
    (net (code "132") (name "unconnected-(SW2-Pad2)") (class "Default")
      (node (ref "SW2") (pin "2") (pinfunction "2_2") (pintype "passive"))
    )
    (net (code "133") (name "unconnected-(SW2-Pad4)") (class "Default")
      (node (ref "SW2") (pin "4") (pinfunction "4_4") (pintype "passive"))
    )
    (net (code "134") (name "unconnected-(SW3-Pad2)") (class "Default")
      (node (ref "SW3") (pin "2") (pinfunction "2_2") (pintype "passive"))
    )
    (net (code "135") (name "unconnected-(SW3-Pad3)") (class "Default")
      (node (ref "SW3") (pin "3") (pinfunction "3_3") (pintype "passive"))
    )
    (net (code "136") (name "unconnected-(U3-Pad1)") (class "Default")
      (node (ref "U3") (pin "1") (pinfunction "1_1") (pintype "passive"))
    )
    (net (code "137") (name "unconnected-(U3-Pad2)") (class "Default")
      (node (ref "U3") (pin "2") (pinfunction "2_2") (pintype "passive"))
    )
    (net (code "138") (name "unconnected-(U3-Pad3)") (class "Default")
      (node (ref "U3") (pin "3") (pinfunction "3_3") (pintype "passive"))
    )
    (net (code "139") (name "unconnected-(U3-Pad4)") (class "Default")
      (node (ref "U3") (pin "4") (pinfunction "4_4") (pintype "passive"))
    )
    (net (code "140") (name "unconnected-(U3-Pad5)") (class "Default")
      (node (ref "U3") (pin "5") (pinfunction "5_5") (pintype "passive"))
    )
    (net (code "141") (name "unconnected-(U3-Pad6)") (class "Default")
      (node (ref "U3") (pin "6") (pinfunction "6_6") (pintype "passive"))
    )
    (net (code "142") (name "unconnected-(U3-Pad7)") (class "Default")
      (node (ref "U3") (pin "7") (pinfunction "7_7") (pintype "passive"))
    )
    (net (code "143") (name "unconnected-(U3-Pad8)") (class "Default")
      (node (ref "U3") (pin "8") (pinfunction "8_8") (pintype "passive"))
    )
  )
)
